# joystick_n_7seg.net
KiCad netlist of a schematic drawn in Altium Designer
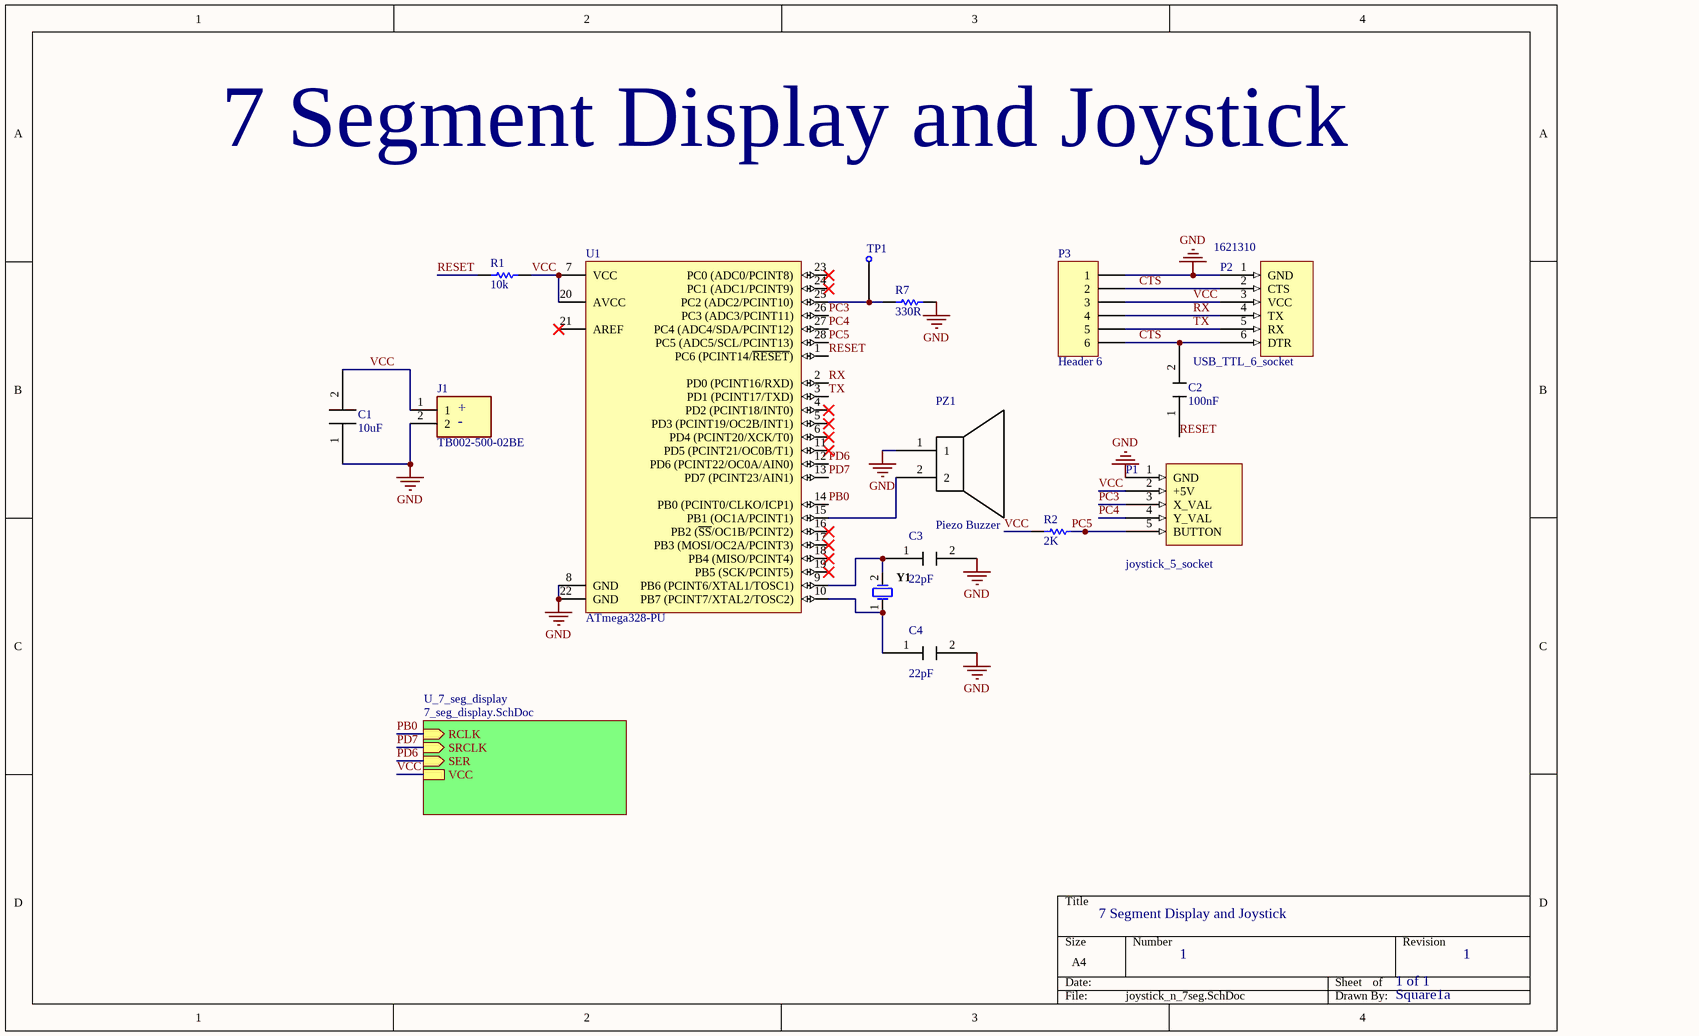
[diagram p0: joystick_n_7seg.SchDoc]

(export (version "E")
  (design (tool "Eeschema 10.0.6"))
  (components
    (comp (ref "C1")
      (value "10uF")
      (footprint "electrolytic_capacitor")
      (libsource (lib "solenoid_maker") (part "electrolytic capacitor"))
    )
    (comp (ref "C2")
      (value "100nF")
      (footprint "Ceramic Capacitor")
      (libsource (lib "shared_schemLib") (part "capacitor"))
    )
    (comp (ref "C3")
      (value "22pF")
      (footprint "Ceramic Capacitor")
      (libsource (lib "shared_schemLib") (part "capacitor"))
    )
    (comp (ref "C4")
      (value "22pF")
      (footprint "Ceramic Capacitor")
      (libsource (lib "shared_schemLib") (part "capacitor"))
    )
    (comp (ref "J1")
      (value "TB002-500-02BE")
      (footprint "CUI_TB002-500-02BE")
      (description "2~24 Poles, Screw Type, Horizontal, 5.0 Pitch, 22~12 (AWG), Terminal Block Connector")
      (fields (field (name "MF") "CUI Devices"))
      (libsource (lib "shared_schemLib") (part "TB002-500-02BE"))
    )
    (comp (ref "P1")
      (value "joystick_5_socket")
      (footprint "joystick")
      (libsource (lib "shared_schemLib") (part "joystick_5_socket"))
    )
    (comp (ref "P2")
      (value "USB_TTL_6_socket")
      (footprint "TTL USB (6 SOCKETS)")
      (fields (field (name "SUPPLIER PART NUMBER 1") "1621310"))
      (libsource (lib "shared_schemLib") (part "USB_TTL_6_socket"))
    )
    (comp (ref "P3")
      (value "Header 6")
      (footprint "HDR1X6")
      (description "Header, 6-Pin")
      (fields (field (name "PUBLISHER") "Altium Limited"))
      (libsource (lib "Miscellaneous Connectors") (part "Header 6"))
    )
    (comp (ref "PZ1")
      (value "Piezo Buzzer")
      (footprint "Buzzer")
      (description "High Temp Piezo Transducer; Resonant Frequency: 4000Hz; Rated Voltage: 5V; SPL @ 10cm: 75dBA")
      (fields
        (field (name "MANUFACTURER") "DB Unlimited")
        (field (name "MANUFACTURER PART NUMBER") "TP124005-2")
      )
      (libsource (lib "shared_schemLib") (part "TP124005-2"))
    )
    (comp (ref "R1")
      (value "10k")
      (footprint "RESA60-630X240")
      (description "Axial Resistor, 100 KOhm, +/- 1%, 0.25 W, -55 to 155 degC, 2-Pin THD, RoHS, Bulk")
      (fields (field (name "TOLERANCE") "1%"))
      (libsource (lib "Altium Content Vault") (part "RES-2"))
    )
    (comp (ref "R2")
      (value "2K")
      (footprint "RESA60-630X240")
      (description "Axial Resistor, 100 KOhm, +/- 1%, 0.25 W, -55 to 155 degC, 2-Pin THD, RoHS, Bulk")
      (fields (field (name "TOLERANCE") "1%"))
      (libsource (lib "Altium Content Vault") (part "RES-2"))
    )
    (comp (ref "R7")
      (value "330R")
      (footprint "RESA60-630X240")
      (description "Axial Resistor, 100 KOhm, +/- 1%, 0.25 W, -55 to 155 degC, 2-Pin THD, RoHS, Bulk")
      (fields (field (name "TOLERANCE") "1%"))
      (libsource (lib "Altium Content Vault") (part "RES-2"))
    )
    (comp (ref "TP1")
      (value "(+5V)")
      (footprint "TEST_POINT")
      (description "Polyurethane Multi-Purpose Cream Adhesive, 10.3 oz Cartridge")
      (fields
        (field (name "MANUFACTURER") "Keystone Electronics")
        (field (name "MANUFACTURER PART NUMBER") "5010")
      )
      (libsource (lib "shared_schemLib") (part "Testpoint"))
    )
    (comp (ref "U1")
      (value "ATmega328-PU")
      (footprint "28P3")
      (libsource (lib "Altium Content Vault") (part "MC-8B-ATM48-IL28"))
    )
    (comp (ref "Y1")
      (value "FOXSLF/160-20")
      (footprint "FOX-FOXSLF160-20")
      (description "Resistance Weld Thru-Hole Crystal, 16 MHz, -20 to 70 degC, 2-Pin THD, RoHS, Bulk")
      (fields (field (name "TOLERANCE") "1%"))
      (libsource (lib "Altium Content Vault") (part "XTAL-1-2-2"))
    )
  )
  (nets
    (net (code "1") (name "/CTS") (class "Default")
      (node (ref "C2") (pin "2") (pinfunction "2_2") (pintype "passive"))
      (node (ref "P2") (pin "2") (pinfunction "CTS_2") (pintype "input"))
      (node (ref "P2") (pin "6") (pinfunction "DTR_6") (pintype "input"))
      (node (ref "P3") (pin "2") (pinfunction "2_2") (pintype "passive"))
      (node (ref "P3") (pin "6") (pinfunction "6_6") (pintype "passive"))
    )
    (net (code "2") (name "/PB0") (class "Default")
      (node (ref "U1") (pin "14") (pinfunction "PB0_(PCINT0/CLKO/ICP1)_14") (pintype "bidirectional"))
    )
    (net (code "3") (name "/PC3") (class "Default")
      (node (ref "P1") (pin "3") (pinfunction "X_VAL_3") (pintype "input"))
      (node (ref "U1") (pin "26") (pinfunction "PC3_(ADC3/PCINT11)_26") (pintype "bidirectional"))
    )
    (net (code "4") (name "/PC4") (class "Default")
      (node (ref "P1") (pin "4") (pinfunction "Y_VAL_4") (pintype "input"))
      (node (ref "U1") (pin "27") (pinfunction "PC4_(ADC4/SDA/PCINT12)_27") (pintype "bidirectional"))
    )
    (net (code "5") (name "/PC5") (class "Default")
      (node (ref "P1") (pin "5") (pinfunction "BUTTON_5") (pintype "input"))
      (node (ref "R2") (pin "1") (pinfunction "1_1") (pintype "passive"))
      (node (ref "U1") (pin "28") (pinfunction "PC5_(ADC5/SCL/PCINT13)_28") (pintype "bidirectional"))
    )
    (net (code "6") (name "/PD6") (class "Default")
      (node (ref "U1") (pin "12") (pinfunction "PD6_(PCINT22/OC0A/AIN0)_12") (pintype "bidirectional"))
    )
    (net (code "7") (name "/PD7") (class "Default")
      (node (ref "U1") (pin "13") (pinfunction "PD7_(PCINT23/AIN1)_13") (pintype "bidirectional"))
    )
    (net (code "8") (name "/RESET") (class "Default")
      (node (ref "C2") (pin "1") (pinfunction "1_1") (pintype "passive"))
      (node (ref "R1") (pin "2") (pinfunction "2_2") (pintype "passive"))
      (node (ref "U1") (pin "1") (pinfunction "PC6_(PCINT14/~{RESET})_1") (pintype "bidirectional"))
    )
    (net (code "9") (name "/RX") (class "Default")
      (node (ref "P2") (pin "4") (pinfunction "TX_4") (pintype "input"))
      (node (ref "P3") (pin "4") (pinfunction "4_4") (pintype "passive"))
      (node (ref "U1") (pin "2") (pinfunction "PD0_(PCINT16/RXD)_2") (pintype "bidirectional"))
    )
    (net (code "10") (name "/TX") (class "Default")
      (node (ref "P2") (pin "5") (pinfunction "RX_5") (pintype "input"))
      (node (ref "P3") (pin "5") (pinfunction "5_5") (pintype "passive"))
      (node (ref "U1") (pin "3") (pinfunction "PD1_(PCINT17/TXD)_3") (pintype "bidirectional"))
    )
    (net (code "11") (name "/VCC") (class "Default")
      (node (ref "C1") (pin "2") (pinfunction "2_2") (pintype "passive"))
      (node (ref "J1") (pin "1") (pinfunction "1_1") (pintype "passive"))
      (node (ref "P1") (pin "2") (pinfunction "+5V_2") (pintype "input"))
      (node (ref "P2") (pin "3") (pinfunction "VCC_3") (pintype "input"))
      (node (ref "P3") (pin "3") (pinfunction "3_3") (pintype "passive"))
      (node (ref "R1") (pin "1") (pinfunction "1_1") (pintype "passive"))
      (node (ref "R2") (pin "2") (pinfunction "2_2") (pintype "passive"))
      (node (ref "U1") (pin "20") (pinfunction "AVCC_20") (pintype "power_in"))
      (node (ref "U1") (pin "7") (pinfunction "VCC_7") (pintype "power_in"))
    )
    (net (code "12") (name "GND") (class "Default")
      (node (ref "C1") (pin "1") (pinfunction "1_1") (pintype "passive"))
      (node (ref "C3") (pin "2") (pinfunction "2_2") (pintype "passive"))
      (node (ref "C4") (pin "2") (pinfunction "2_2") (pintype "passive"))
      (node (ref "J1") (pin "2") (pinfunction "2_2") (pintype "passive"))
      (node (ref "P1") (pin "1") (pinfunction "GND_1") (pintype "input"))
      (node (ref "P2") (pin "1") (pinfunction "GND_1") (pintype "input"))
      (node (ref "P3") (pin "1") (pinfunction "1_1") (pintype "passive"))
      (node (ref "PZ1") (pin "1") (pinfunction "1_1") (pintype "passive"))
      (node (ref "R7") (pin "1") (pinfunction "1_1") (pintype "passive"))
      (node (ref "U1") (pin "22") (pinfunction "GND_22") (pintype "power_in"))
      (node (ref "U1") (pin "8") (pinfunction "GND_8") (pintype "power_in"))
    )
    (net (code "13") (name "Net-(U1-PB1_(OC1A{slash}PCINT1))") (class "Default")
      (node (ref "PZ1") (pin "2") (pinfunction "2_2") (pintype "passive"))
      (node (ref "U1") (pin "15") (pinfunction "PB1_(OC1A/PCINT1)_15") (pintype "bidirectional"))
    )
    (net (code "14") (name "Net-(U1-PB6_(PCINT6{slash}XTAL1{slash}TOSC1))") (class "Default")
      (node (ref "C3") (pin "1") (pinfunction "1_1") (pintype "passive"))
      (node (ref "U1") (pin "9") (pinfunction "PB6_(PCINT6/XTAL1/TOSC1)_9") (pintype "bidirectional"))
      (node (ref "Y1") (pin "2") (pinfunction "2_2") (pintype "passive"))
    )
    (net (code "15") (name "Net-(U1-PB7_(PCINT7{slash}XTAL2{slash}TOSC2))") (class "Default")
      (node (ref "C4") (pin "1") (pinfunction "1_1") (pintype "passive"))
      (node (ref "U1") (pin "10") (pinfunction "PB7_(PCINT7/XTAL2/TOSC2)_10") (pintype "bidirectional"))
      (node (ref "Y1") (pin "1") (pinfunction "1_1") (pintype "passive"))
    )
    (net (code "16") (name "Net-(U1-PC2_(ADC2{slash}PCINT10))") (class "Default")
      (node (ref "R7") (pin "2") (pinfunction "2_2") (pintype "passive"))
      (node (ref "TP1") (pin "1") (pinfunction "1_1") (pintype "passive"))
      (node (ref "U1") (pin "25") (pinfunction "PC2_(ADC2/PCINT10)_25") (pintype "bidirectional"))
    )
    (net (code "17") (name "unconnected-(U1-AREF-Pad21)") (class "Default")
      (node (ref "U1") (pin "21") (pinfunction "AREF_21") (pintype "power_in+no_connect"))
    )
    (net (code "18") (name "unconnected-(U1-PB2_(~{SS}{slash}OC1B{slash}PCINT2)-Pad16)") (class "Default")
      (node (ref "U1") (pin "16") (pinfunction "PB2_(~{SS}/OC1B/PCINT2)_16") (pintype "bidirectional+no_connect"))
    )
    (net (code "19") (name "unconnected-(U1-PB3_(MOSI{slash}OC2A{slash}PCINT3)-Pad17)") (class "Default")
      (node (ref "U1") (pin "17") (pinfunction "PB3_(MOSI/OC2A/PCINT3)_17") (pintype "bidirectional+no_connect"))
    )
    (net (code "20") (name "unconnected-(U1-PB4_(MISO{slash}PCINT4)-Pad18)") (class "Default")
      (node (ref "U1") (pin "18") (pinfunction "PB4_(MISO/PCINT4)_18") (pintype "bidirectional+no_connect"))
    )
    (net (code "21") (name "unconnected-(U1-PB5_(SCK{slash}PCINT5)-Pad19)") (class "Default")
      (node (ref "U1") (pin "19") (pinfunction "PB5_(SCK/PCINT5)_19") (pintype "bidirectional+no_connect"))
    )
    (net (code "22") (name "unconnected-(U1-PC0_(ADC0{slash}PCINT8)-Pad23)") (class "Default")
      (node (ref "U1") (pin "23") (pinfunction "PC0_(ADC0/PCINT8)_23") (pintype "bidirectional+no_connect"))
    )
    (net (code "23") (name "unconnected-(U1-PC1_(ADC1{slash}PCINT9)-Pad24)") (class "Default")
      (node (ref "U1") (pin "24") (pinfunction "PC1_(ADC1/PCINT9)_24") (pintype "bidirectional+no_connect"))
    )
    (net (code "24") (name "unconnected-(U1-PD2_(PCINT18{slash}INT0)-Pad4)") (class "Default")
      (node (ref "U1") (pin "4") (pinfunction "PD2_(PCINT18/INT0)_4") (pintype "bidirectional+no_connect"))
    )
    (net (code "25") (name "unconnected-(U1-PD3_(PCINT19{slash}OC2B{slash}INT1)-Pad5)") (class "Default")
      (node (ref "U1") (pin "5") (pinfunction "PD3_(PCINT19/OC2B/INT1)_5") (pintype "bidirectional+no_connect"))
    )
    (net (code "26") (name "unconnected-(U1-PD4_(PCINT20{slash}XCK{slash}T0)-Pad6)") (class "Default")
      (node (ref "U1") (pin "6") (pinfunction "PD4_(PCINT20/XCK/T0)_6") (pintype "bidirectional+no_connect"))
    )
    (net (code "27") (name "unconnected-(U1-PD5_(PCINT21{slash}OC0B{slash}T1)-Pad11)") (class "Default")
      (node (ref "U1") (pin "11") (pinfunction "PD5_(PCINT21/OC0B/T1)_11") (pintype "bidirectional+no_connect"))
    )
  )
)
